# PVDF_Drone.net
KiCad netlist of a schematic drawn in Altium Designer
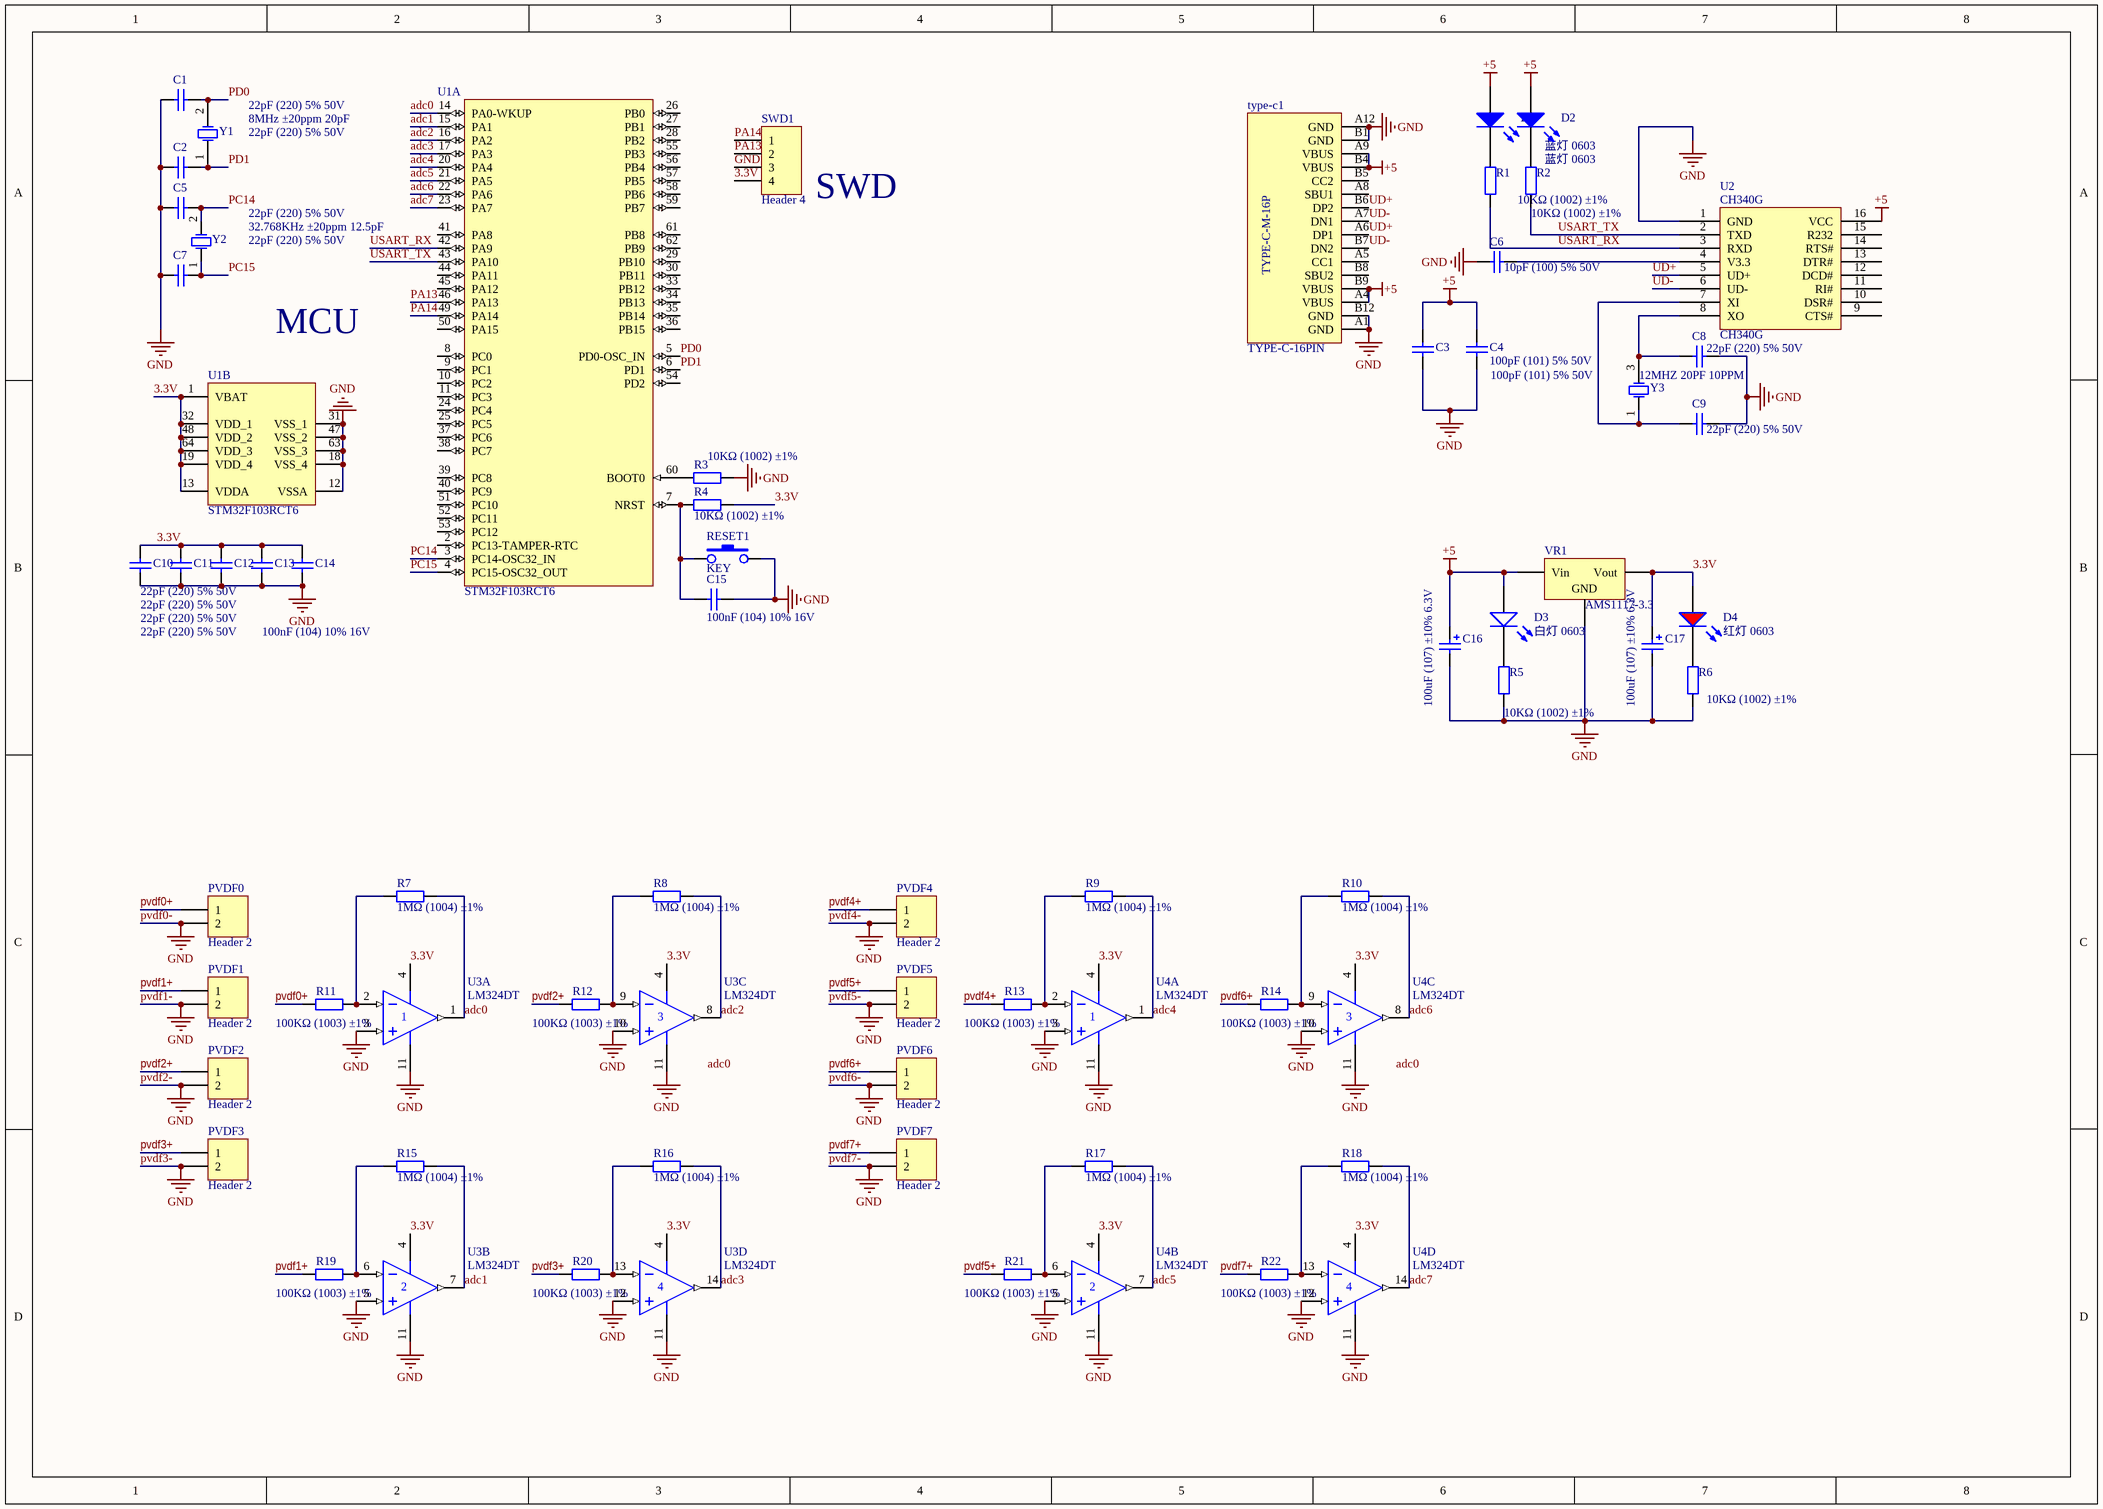
[diagram p0: PVDF_Drone.SchDoc]

(export (version "E")
  (design (tool "Eeschema 10.0.6"))
  (components
    (comp (ref "C1")
      (value "22pF (220) 5% 50V")
      (footprint "0402_C")
      (description "贴片电容")
      (libsource (lib "Miscellaneous Devices LC") (part "0402 22pF (220) 5% 50V"))
    )
    (comp (ref "C2")
      (value "22pF (220) 5% 50V")
      (footprint "0402_C")
      (description "贴片电容")
      (libsource (lib "Miscellaneous Devices LC") (part "0402 22pF (220) 5% 50V"))
    )
    (comp (ref "C3")
      (value "100pF (101) 5% 50V")
      (footprint "0402_C")
      (description "贴片电容")
      (libsource (lib "Miscellaneous Devices LC") (part "0402 100pF (101) 5% 50V"))
    )
    (comp (ref "C4")
      (value "100pF (101) 5% 50V")
      (footprint "0402_C")
      (description "贴片电容")
      (libsource (lib "Miscellaneous Devices LC") (part "0402 100pF (101) 5% 50V"))
    )
    (comp (ref "C5")
      (value "22pF (220) 5% 50V")
      (footprint "0402_C")
      (description "贴片电容")
      (libsource (lib "Miscellaneous Devices LC") (part "0402 22pF (220) 5% 50V"))
    )
    (comp (ref "C6")
      (value "10pF (100) 5% 50V")
      (footprint "0402_C")
      (description "贴片电容")
      (libsource (lib "Miscellaneous Devices LC") (part "0402 10pF (100) 5% 50V"))
    )
    (comp (ref "C7")
      (value "22pF (220) 5% 50V")
      (footprint "0402_C")
      (description "贴片电容")
      (libsource (lib "Miscellaneous Devices LC") (part "0402 22pF (220) 5% 50V"))
    )
    (comp (ref "C8")
      (value "22pF (220) 5% 50V")
      (footprint "0402_C")
      (description "贴片电容")
      (libsource (lib "Miscellaneous Devices LC") (part "0402 22pF (220) 5% 50V"))
    )
    (comp (ref "C9")
      (value "22pF (220) 5% 50V")
      (footprint "0402_C")
      (description "贴片电容")
      (libsource (lib "Miscellaneous Devices LC") (part "0402 22pF (220) 5% 50V"))
    )
    (comp (ref "C10")
      (value "100nF (104) 10% 16V")
      (footprint "0402_C")
      (description "贴片电容")
      (libsource (lib "Miscellaneous Devices LC") (part "0402 100nF (104) 10% 16V"))
    )
    (comp (ref "C11")
      (value "22pF (220) 5% 50V")
      (footprint "0402_C")
      (description "贴片电容")
      (libsource (lib "Miscellaneous Devices LC") (part "0402 22pF (220) 5% 50V"))
    )
    (comp (ref "C12")
      (value "22pF (220) 5% 50V")
      (footprint "0402_C")
      (description "贴片电容")
      (libsource (lib "Miscellaneous Devices LC") (part "0402 22pF (220) 5% 50V"))
    )
    (comp (ref "C13")
      (value "22pF (220) 5% 50V")
      (footprint "0402_C")
      (description "贴片电容")
      (libsource (lib "Miscellaneous Devices LC") (part "0402 22pF (220) 5% 50V"))
    )
    (comp (ref "C14")
      (value "22pF (220) 5% 50V")
      (footprint "0402_C")
      (description "贴片电容")
      (libsource (lib "Miscellaneous Devices LC") (part "0402 22pF (220) 5% 50V"))
    )
    (comp (ref "C15")
      (value "100nF (104) 10% 16V")
      (footprint "0402_C")
      (description "贴片电容")
      (libsource (lib "Miscellaneous Devices LC") (part "0402 100nF (104) 10% 16V"))
    )
    (comp (ref "C16")
      (value "100uF (107) ±10% 6.3V")
      (footprint "CASE-B_3528")
      (description "钽电容")
      (libsource (lib "Miscellaneous Devices LC") (part "3528 100uF (107) 10% 6.3V"))
    )
    (comp (ref "C17")
      (value "100uF (107) ±10% 6.3V")
      (footprint "CASE-B_3528")
      (description "钽电容")
      (libsource (lib "Miscellaneous Devices LC") (part "3528 100uF (107) 10% 6.3V"))
    )
    (comp (ref "D1")
      (value "蓝灯 0603")
      (footprint "0603_LED_S1")
      (description "发光二极管")
      (libsource (lib "Miscellaneous Devices LC") (part "0603 蓝灯"))
    )
    (comp (ref "D2")
      (value "蓝灯 0603")
      (footprint "0603_LED_S1")
      (description "发光二极管")
      (libsource (lib "Miscellaneous Devices LC") (part "0603 蓝灯"))
    )
    (comp (ref "D3")
      (value "白灯 0603")
      (footprint "0603_LED_S1")
      (description "发光二极管")
      (libsource (lib "Miscellaneous Devices LC") (part "0603 白灯"))
    )
    (comp (ref "D4")
      (value "红灯 0603")
      (footprint "0603_LED_S1")
      (description "发光二极管")
      (libsource (lib "Miscellaneous Devices LC") (part "0603 红灯"))
    )
    (comp (ref "PVDF0")
      (value "Header 2")
      (footprint "Pin HDR1X2/2.54mm-S")
      (description "Header, 2-Pin")
      (fields (field (name "PUBLISHER") "Altium Limited"))
      (libsource (lib "Miscellaneous Connectors") (part "Header 2"))
    )
    (comp (ref "PVDF1")
      (value "Header 2")
      (footprint "Pin HDR1X2/2.54mm-S")
      (description "Header, 2-Pin")
      (fields (field (name "PUBLISHER") "Altium Limited"))
      (libsource (lib "Miscellaneous Connectors") (part "Header 2"))
    )
    (comp (ref "PVDF2")
      (value "Header 2")
      (footprint "Pin HDR1X2/2.54mm-S")
      (description "Header, 2-Pin")
      (fields (field (name "PUBLISHER") "Altium Limited"))
      (libsource (lib "Miscellaneous Connectors") (part "Header 2"))
    )
    (comp (ref "PVDF3")
      (value "Header 2")
      (footprint "Pin HDR1X2/2.54mm-S")
      (description "Header, 2-Pin")
      (fields (field (name "PUBLISHER") "Altium Limited"))
      (libsource (lib "Miscellaneous Connectors") (part "Header 2"))
    )
    (comp (ref "PVDF4")
      (value "Header 2")
      (footprint "Pin HDR1X2/2.54mm-S")
      (description "Header, 2-Pin")
      (fields (field (name "PUBLISHER") "Altium Limited"))
      (libsource (lib "Miscellaneous Connectors") (part "Header 2"))
    )
    (comp (ref "PVDF5")
      (value "Header 2")
      (footprint "Pin HDR1X2/2.54mm-S")
      (description "Header, 2-Pin")
      (fields (field (name "PUBLISHER") "Altium Limited"))
      (libsource (lib "Miscellaneous Connectors") (part "Header 2"))
    )
    (comp (ref "PVDF6")
      (value "Header 2")
      (footprint "Pin HDR1X2/2.54mm-S")
      (description "Header, 2-Pin")
      (fields (field (name "PUBLISHER") "Altium Limited"))
      (libsource (lib "Miscellaneous Connectors") (part "Header 2"))
    )
    (comp (ref "PVDF7")
      (value "Header 2")
      (footprint "Pin HDR1X2/2.54mm-S")
      (description "Header, 2-Pin")
      (fields (field (name "PUBLISHER") "Altium Limited"))
      (libsource (lib "Miscellaneous Connectors") (part "Header 2"))
    )
    (comp (ref "R1")
      (value "10KΩ (1002) ±1%")
      (footprint "0402_R")
      (description "贴片电阻")
      (libsource (lib "Miscellaneous Devices LC") (part "0402 10KΩ (1002) 1%"))
    )
    (comp (ref "R2")
      (value "10KΩ (1002) ±1%")
      (footprint "0402_R")
      (description "贴片电阻")
      (libsource (lib "Miscellaneous Devices LC") (part "0402 10KΩ (1002) 1%"))
    )
    (comp (ref "R3")
      (value "10KΩ (1002) ±1%")
      (footprint "0402_R")
      (description "贴片电阻")
      (libsource (lib "") (part "0402 10KΩ (1002) 1%_1"))
    )
    (comp (ref "R4")
      (value "10KΩ (1002) ±1%")
      (footprint "0402_R")
      (description "贴片电阻")
      (libsource (lib "") (part "0402 10KΩ (1002) 1%_1"))
    )
    (comp (ref "R5")
      (value "10KΩ (1002) ±1%")
      (footprint "0402_R")
      (description "贴片电阻")
      (libsource (lib "Miscellaneous Devices LC") (part "0402 10KΩ (1002) 1%"))
    )
    (comp (ref "R6")
      (value "10KΩ (1002) ±1%")
      (footprint "0402_R")
      (description "贴片电阻")
      (libsource (lib "Miscellaneous Devices LC") (part "0402 10KΩ (1002) 1%"))
    )
    (comp (ref "R7")
      (value "1MΩ (1004) ±1%")
      (footprint "0402_R")
      (description "贴片电阻")
      (libsource (lib "Miscellaneous Devices LC") (part "0402 1MΩ (1004) 1%"))
    )
    (comp (ref "R8")
      (value "1MΩ (1004) ±1%")
      (footprint "0402_R")
      (description "贴片电阻")
      (libsource (lib "Miscellaneous Devices LC") (part "0402 1MΩ (1004) 1%"))
    )
    (comp (ref "R9")
      (value "1MΩ (1004) ±1%")
      (footprint "0402_R")
      (description "贴片电阻")
      (libsource (lib "Miscellaneous Devices LC") (part "0402 1MΩ (1004) 1%"))
    )
    (comp (ref "R10")
      (value "1MΩ (1004) ±1%")
      (footprint "0402_R")
      (description "贴片电阻")
      (libsource (lib "Miscellaneous Devices LC") (part "0402 1MΩ (1004) 1%"))
    )
    (comp (ref "R11")
      (value "100KΩ (1003) ±1%")
      (footprint "0402_R")
      (description "贴片电阻")
      (libsource (lib "Miscellaneous Devices LC") (part "0402 100KΩ (1003) 1%"))
    )
    (comp (ref "R12")
      (value "100KΩ (1003) ±1%")
      (footprint "0402_R")
      (description "贴片电阻")
      (libsource (lib "Miscellaneous Devices LC") (part "0402 100KΩ (1003) 1%"))
    )
    (comp (ref "R13")
      (value "100KΩ (1003) ±1%")
      (footprint "0402_R")
      (description "贴片电阻")
      (libsource (lib "Miscellaneous Devices LC") (part "0402 100KΩ (1003) 1%"))
    )
    (comp (ref "R14")
      (value "100KΩ (1003) ±1%")
      (footprint "0402_R")
      (description "贴片电阻")
      (libsource (lib "Miscellaneous Devices LC") (part "0402 100KΩ (1003) 1%"))
    )
    (comp (ref "R15")
      (value "1MΩ (1004) ±1%")
      (footprint "0402_R")
      (description "贴片电阻")
      (libsource (lib "Miscellaneous Devices LC") (part "0402 1MΩ (1004) 1%"))
    )
    (comp (ref "R16")
      (value "1MΩ (1004) ±1%")
      (footprint "0402_R")
      (description "贴片电阻")
      (libsource (lib "Miscellaneous Devices LC") (part "0402 1MΩ (1004) 1%"))
    )
    (comp (ref "R17")
      (value "1MΩ (1004) ±1%")
      (footprint "0402_R")
      (description "贴片电阻")
      (libsource (lib "Miscellaneous Devices LC") (part "0402 1MΩ (1004) 1%"))
    )
    (comp (ref "R18")
      (value "1MΩ (1004) ±1%")
      (footprint "0402_R")
      (description "贴片电阻")
      (libsource (lib "Miscellaneous Devices LC") (part "0402 1MΩ (1004) 1%"))
    )
    (comp (ref "R19")
      (value "100KΩ (1003) ±1%")
      (footprint "0402_R")
      (description "贴片电阻")
      (libsource (lib "Miscellaneous Devices LC") (part "0402 100KΩ (1003) 1%"))
    )
    (comp (ref "R20")
      (value "100KΩ (1003) ±1%")
      (footprint "0402_R")
      (description "贴片电阻")
      (libsource (lib "Miscellaneous Devices LC") (part "0402 100KΩ (1003) 1%"))
    )
    (comp (ref "R21")
      (value "100KΩ (1003) ±1%")
      (footprint "0402_R")
      (description "贴片电阻")
      (libsource (lib "Miscellaneous Devices LC") (part "0402 100KΩ (1003) 1%"))
    )
    (comp (ref "R22")
      (value "100KΩ (1003) ±1%")
      (footprint "0402_R")
      (description "贴片电阻")
      (libsource (lib "Miscellaneous Devices LC") (part "0402 100KΩ (1003) 1%"))
    )
    (comp (ref "RESET1") (value "KEY") (footprint "SMD-3X6X2.5") (libsource (lib "轻触开关") (part "KEY")))
    (comp (ref "SWD1")
      (value "Header 4")
      (footprint "Pin HDR1X4/2.54mm-S")
      (description "Header, 4-Pin")
      (fields (field (name "PUBLISHER") "Altium Limited"))
      (libsource (lib "Miscellaneous Connectors") (part "Header 4"))
    )
    (comp (ref "type-c1")
      (value "TYPE-C-16PIN")
      (footprint "TYPE-C-M-16PIN")
      (fields (field (name "PUBLISHER") "Altium Limited"))
      (libsource (lib "USB-TYPEC-M-16PIN") (part "TYPE-C-16PIN"))
    )
    (comp (ref "U1")
      (value "STM32F103RCT6")
      (footprint "LQFP-64_10x10x05P")
      (description "ARM")
      (libsource (lib "Miscellaneous Devices LC") (part "STM32F103RCT6"))
    )
    (comp (ref "U2")
      (value "CH340G")
      (footprint "SOIC-16_150mil")
      (description "USB")
      (libsource (lib "Miscellaneous Devices LC") (part "CH340G_[C14267]"))
    )
    (comp (ref "U3")
      (value "LM324DT")
      (footprint "SOIC-14_150mil")
      (description "运放")
      (libsource (lib "Miscellaneous Devices LC") (part "LM324DT_[C71035]"))
    )
    (comp (ref "U4")
      (value "LM324DT")
      (footprint "SOIC-14_150mil")
      (description "运放")
      (libsource (lib "Miscellaneous Devices LC") (part "LM324DT_[C71035]"))
    )
    (comp (ref "VR1")
      (value "AMS1117-3.3")
      (footprint "SOT-223")
      (description "低压差线性稳压(LDO)")
      (libsource (lib "Miscellaneous Devices LC") (part "SOT-223 AMS1117-3.3"))
    )
    (comp (ref "Y1")
      (value "8MHz ±20ppm 20pF")
      (footprint "SMD-5032_2P")
      (description "贴片晶振")
      (libsource (lib "Miscellaneous Devices LC") (part "SMD-5032_2P 8MHz 20ppm 20pF"))
    )
    (comp (ref "Y2")
      (value "32.768KHz ±20ppm 12.5pF")
      (footprint "SMD-3215_2P FC - 135")
      (description "贴片晶振")
      (libsource (lib "Miscellaneous Devices LC") (part "SMD-3215_2P 32.768KHz 20ppm 12.5pF"))
    )
    (comp (ref "Y3")
      (value "12MHZ 20PF 10PPM")
      (footprint "SMD-3225_4P")
      (description "贴片晶振")
      (libsource (lib "Miscellaneous Devices LC") (part "SMD-3225_4P  12MHZ 20PF 10PPM"))
    )
  )
  (nets
    (net (code "1") (name "+5") (class "Default")
      (node (ref "C16") (pin "1") (pinfunction "1_1") (pintype "passive"))
      (node (ref "C3") (pin "2") (pinfunction "2_2") (pintype "passive"))
      (node (ref "C4") (pin "2") (pinfunction "2_2") (pintype "passive"))
      (node (ref "D1") (pin "A") (pinfunction "A_A") (pintype "passive"))
      (node (ref "D2") (pin "A") (pinfunction "A_A") (pintype "passive"))
      (node (ref "D3") (pin "A") (pinfunction "A_A") (pintype "passive"))
      (node (ref "U2") (pin "16") (pinfunction "VCC_16") (pintype "passive"))
      (node (ref "VR1") (pin "3") (pinfunction "Vin_3") (pintype "passive"))
      (node (ref "type-c1") (pin "A4") (pinfunction "VBUS_A4") (pintype "passive"))
      (node (ref "type-c1") (pin "A9") (pinfunction "VBUS_A9") (pintype "passive"))
      (node (ref "type-c1") (pin "B4") (pinfunction "VBUS_B4") (pintype "passive"))
      (node (ref "type-c1") (pin "B9") (pinfunction "VBUS_B9") (pintype "passive"))
    )
    (net (code "2") (name "/3.3V") (class "Default")
      (node (ref "C10") (pin "2") (pinfunction "2_2") (pintype "passive"))
      (node (ref "C11") (pin "2") (pinfunction "2_2") (pintype "passive"))
      (node (ref "C12") (pin "2") (pinfunction "2_2") (pintype "passive"))
      (node (ref "C13") (pin "2") (pinfunction "2_2") (pintype "passive"))
      (node (ref "C14") (pin "2") (pinfunction "2_2") (pintype "passive"))
      (node (ref "C17") (pin "1") (pinfunction "1_1") (pintype "passive"))
      (node (ref "D4") (pin "A") (pinfunction "A_A") (pintype "passive"))
      (node (ref "R4") (pin "1") (pinfunction "1_1") (pintype "passive"))
      (node (ref "SWD1") (pin "4") (pinfunction "4_4") (pintype "passive"))
      (node (ref "U1") (pin "1") (pinfunction "VBAT_1") (pintype "power_in"))
      (node (ref "U1") (pin "13") (pinfunction "VDDA_13") (pintype "power_in"))
      (node (ref "U1") (pin "19") (pinfunction "VDD_4_19") (pintype "power_in"))
      (node (ref "U1") (pin "32") (pinfunction "VDD_1_32") (pintype "power_in"))
      (node (ref "U1") (pin "48") (pinfunction "VDD_2_48") (pintype "power_in"))
      (node (ref "U1") (pin "64") (pinfunction "VDD_3_64") (pintype "power_in"))
      (node (ref "U3") (pin "4") (pinfunction "V+_4") (pintype "power_in"))
      (node (ref "U4") (pin "4") (pinfunction "V+_4") (pintype "power_in"))
      (node (ref "VR1") (pin "2") (pinfunction "Vout_2") (pintype "passive"))
    )
    (net (code "3") (name "/PA13") (class "Default")
      (node (ref "SWD1") (pin "2") (pinfunction "2_2") (pintype "passive"))
      (node (ref "U1") (pin "46") (pinfunction "PA13_46") (pintype "bidirectional"))
    )
    (net (code "4") (name "/PA14") (class "Default")
      (node (ref "SWD1") (pin "1") (pinfunction "1_1") (pintype "passive"))
      (node (ref "U1") (pin "49") (pinfunction "PA14_49") (pintype "bidirectional"))
    )
    (net (code "5") (name "/PC14") (class "Default")
      (node (ref "C5") (pin "2") (pinfunction "2_2") (pintype "passive"))
      (node (ref "U1") (pin "3") (pinfunction "PC14-OSC32_IN_3") (pintype "bidirectional"))
      (node (ref "Y2") (pin "2") (pinfunction "OSC2_2") (pintype "passive"))
    )
    (net (code "6") (name "/PC15") (class "Default")
      (node (ref "C7") (pin "2") (pinfunction "2_2") (pintype "passive"))
      (node (ref "U1") (pin "4") (pinfunction "PC15-OSC32_OUT_4") (pintype "bidirectional"))
      (node (ref "Y2") (pin "1") (pinfunction "OSC1_1") (pintype "passive"))
    )
    (net (code "7") (name "/PD0") (class "Default")
      (node (ref "C1") (pin "2") (pinfunction "2_2") (pintype "passive"))
      (node (ref "U1") (pin "5") (pinfunction "PD0-OSC_IN_5") (pintype "bidirectional"))
      (node (ref "Y1") (pin "2") (pinfunction "OSC2_2") (pintype "passive"))
    )
    (net (code "8") (name "/PD1") (class "Default")
      (node (ref "C2") (pin "2") (pinfunction "2_2") (pintype "passive"))
      (node (ref "U1") (pin "6") (pinfunction "PD1_6") (pintype "bidirectional"))
      (node (ref "Y1") (pin "1") (pinfunction "OSC1_1") (pintype "passive"))
    )
    (net (code "9") (name "/UD+") (class "Default")
      (node (ref "U2") (pin "5") (pinfunction "UD+_5") (pintype "passive"))
      (node (ref "type-c1") (pin "A6") (pinfunction "DP1_A6") (pintype "passive"))
      (node (ref "type-c1") (pin "B6") (pinfunction "DP2_B6") (pintype "passive"))
    )
    (net (code "10") (name "/UD-") (class "Default")
      (node (ref "U2") (pin "6") (pinfunction "UD-_6") (pintype "passive"))
      (node (ref "type-c1") (pin "A7") (pinfunction "DN1_A7") (pintype "passive"))
      (node (ref "type-c1") (pin "B7") (pinfunction "DN2_B7") (pintype "passive"))
    )
    (net (code "11") (name "/USART_RX") (class "Default")
      (node (ref "R1") (pin "1") (pinfunction "1_1") (pintype "passive"))
      (node (ref "U1") (pin "42") (pinfunction "PA9_42") (pintype "bidirectional"))
      (node (ref "U2") (pin "3") (pinfunction "RXD_3") (pintype "passive"))
    )
    (net (code "12") (name "/USART_TX") (class "Default")
      (node (ref "R2") (pin "1") (pinfunction "1_1") (pintype "passive"))
      (node (ref "U1") (pin "43") (pinfunction "PA10_43") (pintype "bidirectional"))
      (node (ref "U2") (pin "2") (pinfunction "TXD_2") (pintype "passive"))
    )
    (net (code "13") (name "/adc0") (class "Default")
      (node (ref "R7") (pin "2") (pinfunction "2_2") (pintype "passive"))
      (node (ref "U1") (pin "14") (pinfunction "PA0-WKUP_14") (pintype "bidirectional"))
      (node (ref "U3") (pin "1") (pinfunction "OUT_1") (pintype "output"))
    )
    (net (code "14") (name "/adc1") (class "Default")
      (node (ref "R15") (pin "2") (pinfunction "2_2") (pintype "passive"))
      (node (ref "U1") (pin "15") (pinfunction "PA1_15") (pintype "bidirectional"))
      (node (ref "U3") (pin "7") (pinfunction "OUT_7") (pintype "output"))
    )
    (net (code "15") (name "/adc2") (class "Default")
      (node (ref "R8") (pin "2") (pinfunction "2_2") (pintype "passive"))
      (node (ref "U1") (pin "16") (pinfunction "PA2_16") (pintype "bidirectional"))
      (node (ref "U3") (pin "8") (pinfunction "OUT_8") (pintype "output"))
    )
    (net (code "16") (name "/adc3") (class "Default")
      (node (ref "R16") (pin "2") (pinfunction "2_2") (pintype "passive"))
      (node (ref "U1") (pin "17") (pinfunction "PA3_17") (pintype "bidirectional"))
      (node (ref "U3") (pin "14") (pinfunction "OUT_14") (pintype "output"))
    )
    (net (code "17") (name "/adc4") (class "Default")
      (node (ref "R9") (pin "2") (pinfunction "2_2") (pintype "passive"))
      (node (ref "U1") (pin "20") (pinfunction "PA4_20") (pintype "bidirectional"))
      (node (ref "U4") (pin "1") (pinfunction "OUT_1") (pintype "output"))
    )
    (net (code "18") (name "/adc5") (class "Default")
      (node (ref "R17") (pin "2") (pinfunction "2_2") (pintype "passive"))
      (node (ref "U1") (pin "21") (pinfunction "PA5_21") (pintype "bidirectional"))
      (node (ref "U4") (pin "7") (pinfunction "OUT_7") (pintype "output"))
    )
    (net (code "19") (name "/adc6") (class "Default")
      (node (ref "R10") (pin "2") (pinfunction "2_2") (pintype "passive"))
      (node (ref "U1") (pin "22") (pinfunction "PA6_22") (pintype "bidirectional"))
      (node (ref "U4") (pin "8") (pinfunction "OUT_8") (pintype "output"))
    )
    (net (code "20") (name "/adc7") (class "Default")
      (node (ref "R18") (pin "2") (pinfunction "2_2") (pintype "passive"))
      (node (ref "U1") (pin "23") (pinfunction "PA7_23") (pintype "bidirectional"))
      (node (ref "U4") (pin "14") (pinfunction "OUT_14") (pintype "output"))
    )
    (net (code "21") (name "/pvdf0+") (class "Default")
      (node (ref "PVDF0") (pin "1") (pinfunction "1_1") (pintype "passive"))
      (node (ref "R11") (pin "1") (pinfunction "1_1") (pintype "passive"))
    )
    (net (code "22") (name "/pvdf1+") (class "Default")
      (node (ref "PVDF1") (pin "1") (pinfunction "1_1") (pintype "passive"))
      (node (ref "R19") (pin "1") (pinfunction "1_1") (pintype "passive"))
    )
    (net (code "23") (name "/pvdf2+") (class "Default")
      (node (ref "PVDF2") (pin "1") (pinfunction "1_1") (pintype "passive"))
      (node (ref "R12") (pin "1") (pinfunction "1_1") (pintype "passive"))
    )
    (net (code "24") (name "/pvdf3+") (class "Default")
      (node (ref "PVDF3") (pin "1") (pinfunction "1_1") (pintype "passive"))
      (node (ref "R20") (pin "1") (pinfunction "1_1") (pintype "passive"))
    )
    (net (code "25") (name "/pvdf4+") (class "Default")
      (node (ref "PVDF4") (pin "1") (pinfunction "1_1") (pintype "passive"))
      (node (ref "R13") (pin "1") (pinfunction "1_1") (pintype "passive"))
    )
    (net (code "26") (name "/pvdf5+") (class "Default")
      (node (ref "PVDF5") (pin "1") (pinfunction "1_1") (pintype "passive"))
      (node (ref "R21") (pin "1") (pinfunction "1_1") (pintype "passive"))
    )
    (net (code "27") (name "/pvdf6+") (class "Default")
      (node (ref "PVDF6") (pin "1") (pinfunction "1_1") (pintype "passive"))
      (node (ref "R14") (pin "1") (pinfunction "1_1") (pintype "passive"))
    )
    (net (code "28") (name "/pvdf7+") (class "Default")
      (node (ref "PVDF7") (pin "1") (pinfunction "1_1") (pintype "passive"))
      (node (ref "R22") (pin "1") (pinfunction "1_1") (pintype "passive"))
    )
    (net (code "29") (name "GND") (class "Default")
      (node (ref "C1") (pin "1") (pinfunction "1_1") (pintype "passive"))
      (node (ref "C10") (pin "1") (pinfunction "1_1") (pintype "passive"))
      (node (ref "C11") (pin "1") (pinfunction "1_1") (pintype "passive"))
      (node (ref "C12") (pin "1") (pinfunction "1_1") (pintype "passive"))
      (node (ref "C13") (pin "1") (pinfunction "1_1") (pintype "passive"))
      (node (ref "C14") (pin "1") (pinfunction "1_1") (pintype "passive"))
      (node (ref "C15") (pin "1") (pinfunction "1_1") (pintype "passive"))
      (node (ref "C16") (pin "2") (pinfunction "2_2") (pintype "passive"))
      (node (ref "C17") (pin "2") (pinfunction "2_2") (pintype "passive"))
      (node (ref "C2") (pin "1") (pinfunction "1_1") (pintype "passive"))
      (node (ref "C3") (pin "1") (pinfunction "1_1") (pintype "passive"))
      (node (ref "C4") (pin "1") (pinfunction "1_1") (pintype "passive"))
      (node (ref "C5") (pin "1") (pinfunction "1_1") (pintype "passive"))
      (node (ref "C6") (pin "1") (pinfunction "1_1") (pintype "passive"))
      (node (ref "C7") (pin "1") (pinfunction "1_1") (pintype "passive"))
      (node (ref "C8") (pin "2") (pinfunction "2_2") (pintype "passive"))
      (node (ref "C9") (pin "2") (pinfunction "2_2") (pintype "passive"))
      (node (ref "PVDF0") (pin "2") (pinfunction "2_2") (pintype "passive"))
      (node (ref "PVDF1") (pin "2") (pinfunction "2_2") (pintype "passive"))
      (node (ref "PVDF2") (pin "2") (pinfunction "2_2") (pintype "passive"))
      (node (ref "PVDF3") (pin "2") (pinfunction "2_2") (pintype "passive"))
      (node (ref "PVDF4") (pin "2") (pinfunction "2_2") (pintype "passive"))
      (node (ref "PVDF5") (pin "2") (pinfunction "2_2") (pintype "passive"))
      (node (ref "PVDF6") (pin "2") (pinfunction "2_2") (pintype "passive"))
      (node (ref "PVDF7") (pin "2") (pinfunction "2_2") (pintype "passive"))
      (node (ref "R3") (pin "1") (pinfunction "1_1") (pintype "passive"))
      (node (ref "R5") (pin "1") (pinfunction "1_1") (pintype "passive"))
      (node (ref "R6") (pin "1") (pinfunction "1_1") (pintype "passive"))
      (node (ref "RESET1") (pin "3") (pinfunction "3_3") (pintype "passive"))
      (node (ref "SWD1") (pin "3") (pinfunction "3_3") (pintype "passive"))
      (node (ref "U1") (pin "12") (pinfunction "VSSA_12") (pintype "power_in"))
      (node (ref "U1") (pin "18") (pinfunction "VSS_4_18") (pintype "power_in"))
      (node (ref "U1") (pin "31") (pinfunction "VSS_1_31") (pintype "power_in"))
      (node (ref "U1") (pin "47") (pinfunction "VSS_2_47") (pintype "power_in"))
      (node (ref "U1") (pin "63") (pinfunction "VSS_3_63") (pintype "power_in"))
      (node (ref "U2") (pin "1") (pinfunction "GND_1") (pintype "passive"))
      (node (ref "U3") (pin "10") (pinfunction "IN+_10") (pintype "input"))
      (node (ref "U3") (pin "11") (pinfunction "V-_11") (pintype "power_in"))
      (node (ref "U3") (pin "12") (pinfunction "IN+_12") (pintype "input"))
      (node (ref "U3") (pin "3") (pinfunction "IN+_3") (pintype "input"))
      (node (ref "U3") (pin "5") (pinfunction "IN+_5") (pintype "input"))
      (node (ref "U4") (pin "10") (pinfunction "IN+_10") (pintype "input"))
      (node (ref "U4") (pin "11") (pinfunction "V-_11") (pintype "power_in"))
      (node (ref "U4") (pin "12") (pinfunction "IN+_12") (pintype "input"))
      (node (ref "U4") (pin "3") (pinfunction "IN+_3") (pintype "input"))
      (node (ref "U4") (pin "5") (pinfunction "IN+_5") (pintype "input"))
      (node (ref "VR1") (pin "1") (pinfunction "GND_1") (pintype "passive"))
      (node (ref "type-c1") (pin "A1") (pinfunction "GND_A1") (pintype "passive"))
      (node (ref "type-c1") (pin "A12") (pinfunction "GND_A12") (pintype "passive"))
      (node (ref "type-c1") (pin "B1") (pinfunction "GND_B1") (pintype "passive"))
      (node (ref "type-c1") (pin "B12") (pinfunction "GND_B12") (pintype "passive"))
    )
    (net (code "30") (name "Net-(D1-PadK)") (class "Default")
      (node (ref "D1") (pin "K") (pinfunction "K_K") (pintype "passive"))
      (node (ref "R1") (pin "2") (pinfunction "2_2") (pintype "passive"))
    )
    (net (code "31") (name "Net-(D2-PadK)") (class "Default")
      (node (ref "D2") (pin "K") (pinfunction "K_K") (pintype "passive"))
      (node (ref "R2") (pin "2") (pinfunction "2_2") (pintype "passive"))
    )
    (net (code "32") (name "Net-(D3-PadK)") (class "Default")
      (node (ref "D3") (pin "K") (pinfunction "K_K") (pintype "passive"))
      (node (ref "R5") (pin "2") (pinfunction "2_2") (pintype "passive"))
    )
    (net (code "33") (name "Net-(D4-PadK)") (class "Default")
      (node (ref "D4") (pin "K") (pinfunction "K_K") (pintype "passive"))
      (node (ref "R6") (pin "2") (pinfunction "2_2") (pintype "passive"))
    )
    (net (code "34") (name "Net-(U1A-BOOT0)") (class "Default")
      (node (ref "R3") (pin "2") (pinfunction "2_2") (pintype "passive"))
      (node (ref "U1") (pin "60") (pinfunction "BOOT0_60") (pintype "input"))
    )
    (net (code "35") (name "Net-(U1A-NRST)") (class "Default")
      (node (ref "C15") (pin "2") (pinfunction "2_2") (pintype "passive"))
      (node (ref "R4") (pin "2") (pinfunction "2_2") (pintype "passive"))
      (node (ref "RESET1") (pin "1") (pinfunction "1_1") (pintype "passive"))
      (node (ref "U1") (pin "7") (pinfunction "NRST_7") (pintype "bidirectional"))
    )
    (net (code "36") (name "Net-(U2-V3.3)") (class "Default")
      (node (ref "C6") (pin "2") (pinfunction "2_2") (pintype "passive"))
      (node (ref "U2") (pin "4") (pinfunction "V3.3_4") (pintype "passive"))
    )
    (net (code "37") (name "Net-(U2-XI)") (class "Default")
      (node (ref "C9") (pin "1") (pinfunction "1_1") (pintype "passive"))
      (node (ref "U2") (pin "7") (pinfunction "XI_7") (pintype "passive"))
      (node (ref "Y3") (pin "1") (pinfunction "OSC1_1") (pintype "passive"))
    )
    (net (code "38") (name "Net-(U2-XO)") (class "Default")
      (node (ref "C8") (pin "1") (pinfunction "1_1") (pintype "passive"))
      (node (ref "U2") (pin "8") (pinfunction "XO_8") (pintype "passive"))
      (node (ref "Y3") (pin "3") (pinfunction "OSC2_3") (pintype "passive"))
    )
    (net (code "39") (name "Net-(U3A-IN-)") (class "Default")
      (node (ref "R11") (pin "2") (pinfunction "2_2") (pintype "passive"))
      (node (ref "R7") (pin "1") (pinfunction "1_1") (pintype "passive"))
      (node (ref "U3") (pin "2") (pinfunction "IN-_2") (pintype "input"))
    )
    (net (code "40") (name "Net-(U3B-IN-)") (class "Default")
      (node (ref "R15") (pin "1") (pinfunction "1_1") (pintype "passive"))
      (node (ref "R19") (pin "2") (pinfunction "2_2") (pintype "passive"))
      (node (ref "U3") (pin "6") (pinfunction "IN-_6") (pintype "input"))
    )
    (net (code "41") (name "Net-(U3C-IN-)") (class "Default")
      (node (ref "R12") (pin "2") (pinfunction "2_2") (pintype "passive"))
      (node (ref "R8") (pin "1") (pinfunction "1_1") (pintype "passive"))
      (node (ref "U3") (pin "9") (pinfunction "IN-_9") (pintype "input"))
    )
    (net (code "42") (name "Net-(U3D-IN-)") (class "Default")
      (node (ref "R16") (pin "1") (pinfunction "1_1") (pintype "passive"))
      (node (ref "R20") (pin "2") (pinfunction "2_2") (pintype "passive"))
      (node (ref "U3") (pin "13") (pinfunction "IN-_13") (pintype "input"))
    )
    (net (code "43") (name "Net-(U4A-IN-)") (class "Default")
      (node (ref "R13") (pin "2") (pinfunction "2_2") (pintype "passive"))
      (node (ref "R9") (pin "1") (pinfunction "1_1") (pintype "passive"))
      (node (ref "U4") (pin "2") (pinfunction "IN-_2") (pintype "input"))
    )
    (net (code "44") (name "Net-(U4B-IN-)") (class "Default")
      (node (ref "R17") (pin "1") (pinfunction "1_1") (pintype "passive"))
      (node (ref "R21") (pin "2") (pinfunction "2_2") (pintype "passive"))
      (node (ref "U4") (pin "6") (pinfunction "IN-_6") (pintype "input"))
    )
    (net (code "45") (name "Net-(U4C-IN-)") (class "Default")
      (node (ref "R10") (pin "1") (pinfunction "1_1") (pintype "passive"))
      (node (ref "R14") (pin "2") (pinfunction "2_2") (pintype "passive"))
      (node (ref "U4") (pin "9") (pinfunction "IN-_9") (pintype "input"))
    )
    (net (code "46") (name "Net-(U4D-IN-)") (class "Default")
      (node (ref "R18") (pin "1") (pinfunction "1_1") (pintype "passive"))
      (node (ref "R22") (pin "2") (pinfunction "2_2") (pintype "passive"))
      (node (ref "U4") (pin "13") (pinfunction "IN-_13") (pintype "input"))
    )
    (net (code "47") (name "unconnected-(U1A-PA8-Pad41)") (class "Default")
      (node (ref "U1") (pin "41") (pinfunction "PA8_41") (pintype "bidirectional"))
    )
    (net (code "48") (name "unconnected-(U1A-PA11-Pad44)") (class "Default")
      (node (ref "U1") (pin "44") (pinfunction "PA11_44") (pintype "bidirectional"))
    )
    (net (code "49") (name "unconnected-(U1A-PA12-Pad45)") (class "Default")
      (node (ref "U1") (pin "45") (pinfunction "PA12_45") (pintype "bidirectional"))
    )
    (net (code "50") (name "unconnected-(U1A-PA15-Pad50)") (class "Default")
      (node (ref "U1") (pin "50") (pinfunction "PA15_50") (pintype "bidirectional"))
    )
    (net (code "51") (name "unconnected-(U1A-PB0-Pad26)") (class "Default")
      (node (ref "U1") (pin "26") (pinfunction "PB0_26") (pintype "bidirectional"))
    )
    (net (code "52") (name "unconnected-(U1A-PB1-Pad27)") (class "Default")
      (node (ref "U1") (pin "27") (pinfunction "PB1_27") (pintype "bidirectional"))
    )
    (net (code "53") (name "unconnected-(U1A-PB2-Pad28)") (class "Default")
      (node (ref "U1") (pin "28") (pinfunction "PB2_28") (pintype "bidirectional"))
    )
    (net (code "54") (name "unconnected-(U1A-PB3-Pad55)") (class "Default")
      (node (ref "U1") (pin "55") (pinfunction "PB3_55") (pintype "bidirectional"))
    )
    (net (code "55") (name "unconnected-(U1A-PB4-Pad56)") (class "Default")
      (node (ref "U1") (pin "56") (pinfunction "PB4_56") (pintype "bidirectional"))
    )
    (net (code "56") (name "unconnected-(U1A-PB5-Pad57)") (class "Default")
      (node (ref "U1") (pin "57") (pinfunction "PB5_57") (pintype "bidirectional"))
    )
    (net (code "57") (name "unconnected-(U1A-PB6-Pad58)") (class "Default")
      (node (ref "U1") (pin "58") (pinfunction "PB6_58") (pintype "bidirectional"))
    )
    (net (code "58") (name "unconnected-(U1A-PB7-Pad59)") (class "Default")
      (node (ref "U1") (pin "59") (pinfunction "PB7_59") (pintype "bidirectional"))
    )
    (net (code "59") (name "unconnected-(U1A-PB8-Pad61)") (class "Default")
      (node (ref "U1") (pin "61") (pinfunction "PB8_61") (pintype "bidirectional"))
    )
    (net (code "60") (name "unconnected-(U1A-PB9-Pad62)") (class "Default")
      (node (ref "U1") (pin "62") (pinfunction "PB9_62") (pintype "bidirectional"))
    )
    (net (code "61") (name "unconnected-(U1A-PB10-Pad29)") (class "Default")
      (node (ref "U1") (pin "29") (pinfunction "PB10_29") (pintype "bidirectional"))
    )
    (net (code "62") (name "unconnected-(U1A-PB11-Pad30)") (class "Default")
      (node (ref "U1") (pin "30") (pinfunction "PB11_30") (pintype "bidirectional"))
    )
    (net (code "63") (name "unconnected-(U1A-PB12-Pad33)") (class "Default")
      (node (ref "U1") (pin "33") (pinfunction "PB12_33") (pintype "bidirectional"))
    )
    (net (code "64") (name "unconnected-(U1A-PB13-Pad34)") (class "Default")
      (node (ref "U1") (pin "34") (pinfunction "PB13_34") (pintype "bidirectional"))
    )
    (net (code "65") (name "unconnected-(U1A-PB14-Pad35)") (class "Default")
      (node (ref "U1") (pin "35") (pinfunction "PB14_35") (pintype "bidirectional"))
    )
    (net (code "66") (name "unconnected-(U1A-PB15-Pad36)") (class "Default")
      (node (ref "U1") (pin "36") (pinfunction "PB15_36") (pintype "bidirectional"))
    )
    (net (code "67") (name "unconnected-(U1A-PC0-Pad8)") (class "Default")
      (node (ref "U1") (pin "8") (pinfunction "PC0_8") (pintype "bidirectional"))
    )
    (net (code "68") (name "unconnected-(U1A-PC1-Pad9)") (class "Default")
      (node (ref "U1") (pin "9") (pinfunction "PC1_9") (pintype "bidirectional"))
    )
    (net (code "69") (name "unconnected-(U1A-PC2-Pad10)") (class "Default")
      (node (ref "U1") (pin "10") (pinfunction "PC2_10") (pintype "bidirectional"))
    )
    (net (code "70") (name "unconnected-(U1A-PC3-Pad11)") (class "Default")
      (node (ref "U1") (pin "11") (pinfunction "PC3_11") (pintype "bidirectional"))
    )
    (net (code "71") (name "unconnected-(U1A-PC4-Pad24)") (class "Default")
      (node (ref "U1") (pin "24") (pinfunction "PC4_24") (pintype "bidirectional"))
    )
    (net (code "72") (name "unconnected-(U1A-PC5-Pad25)") (class "Default")
      (node (ref "U1") (pin "25") (pinfunction "PC5_25") (pintype "bidirectional"))
    )
    (net (code "73") (name "unconnected-(U1A-PC6-Pad37)") (class "Default")
      (node (ref "U1") (pin "37") (pinfunction "PC6_37") (pintype "bidirectional"))
    )
    (net (code "74") (name "unconnected-(U1A-PC7-Pad38)") (class "Default")
      (node (ref "U1") (pin "38") (pinfunction "PC7_38") (pintype "bidirectional"))
    )
    (net (code "75") (name "unconnected-(U1A-PC8-Pad39)") (class "Default")
      (node (ref "U1") (pin "39") (pinfunction "PC8_39") (pintype "bidirectional"))
    )
    (net (code "76") (name "unconnected-(U1A-PC9-Pad40)") (class "Default")
      (node (ref "U1") (pin "40") (pinfunction "PC9_40") (pintype "bidirectional"))
    )
    (net (code "77") (name "unconnected-(U1A-PC10-Pad51)") (class "Default")
      (node (ref "U1") (pin "51") (pinfunction "PC10_51") (pintype "bidirectional"))
    )
    (net (code "78") (name "unconnected-(U1A-PC11-Pad52)") (class "Default")
      (node (ref "U1") (pin "52") (pinfunction "PC11_52") (pintype "bidirectional"))
    )
    (net (code "79") (name "unconnected-(U1A-PC12-Pad53)") (class "Default")
      (node (ref "U1") (pin "53") (pinfunction "PC12_53") (pintype "bidirectional"))
    )
    (net (code "80") (name "unconnected-(U1A-PC13-TAMPER-RTC-Pad2)") (class "Default")
      (node (ref "U1") (pin "2") (pinfunction "PC13-TAMPER-RTC_2") (pintype "bidirectional"))
    )
    (net (code "81") (name "unconnected-(U1A-PD2-Pad54)") (class "Default")
      (node (ref "U1") (pin "54") (pinfunction "PD2_54") (pintype "bidirectional"))
    )
    (net (code "82") (name "unconnected-(U2-CTS#-Pad9)") (class "Default")
      (node (ref "U2") (pin "9") (pinfunction "CTS#_9") (pintype "passive"))
    )
    (net (code "83") (name "unconnected-(U2-DCD#-Pad12)") (class "Default")
      (node (ref "U2") (pin "12") (pinfunction "DCD#_12") (pintype "passive"))
    )
    (net (code "84") (name "unconnected-(U2-DSR#-Pad10)") (class "Default")
      (node (ref "U2") (pin "10") (pinfunction "DSR#_10") (pintype "passive"))
    )
    (net (code "85") (name "unconnected-(U2-DTR#-Pad13)") (class "Default")
      (node (ref "U2") (pin "13") (pinfunction "DTR#_13") (pintype "passive"))
    )
    (net (code "86") (name "unconnected-(U2-R232-Pad15)") (class "Default")
      (node (ref "U2") (pin "15") (pinfunction "R232_15") (pintype "passive"))
    )
    (net (code "87") (name "unconnected-(U2-RI#-Pad11)") (class "Default")
      (node (ref "U2") (pin "11") (pinfunction "RI#_11") (pintype "passive"))
    )
    (net (code "88") (name "unconnected-(U2-RTS#-Pad14)") (class "Default")
      (node (ref "U2") (pin "14") (pinfunction "RTS#_14") (pintype "passive"))
    )
    (net (code "89") (name "unconnected-(type-c1-CC1-PadA5)") (class "Default")
      (node (ref "type-c1") (pin "A5") (pinfunction "CC1_A5") (pintype "passive"))
    )
    (net (code "90") (name "unconnected-(type-c1-CC2-PadB5)") (class "Default")
      (node (ref "type-c1") (pin "B5") (pinfunction "CC2_B5") (pintype "passive"))
    )
    (net (code "91") (name "unconnected-(type-c1-SBU1-PadA8)") (class "Default")
      (node (ref "type-c1") (pin "A8") (pinfunction "SBU1_A8") (pintype "passive"))
    )
    (net (code "92") (name "unconnected-(type-c1-SBU2-PadB8)") (class "Default")
      (node (ref "type-c1") (pin "B8") (pinfunction "SBU2_B8") (pintype "passive"))
    )
  )
)
